# MAX3485_TXB0108PWR.net
KiCad netlist of a schematic drawn in Altium Designer
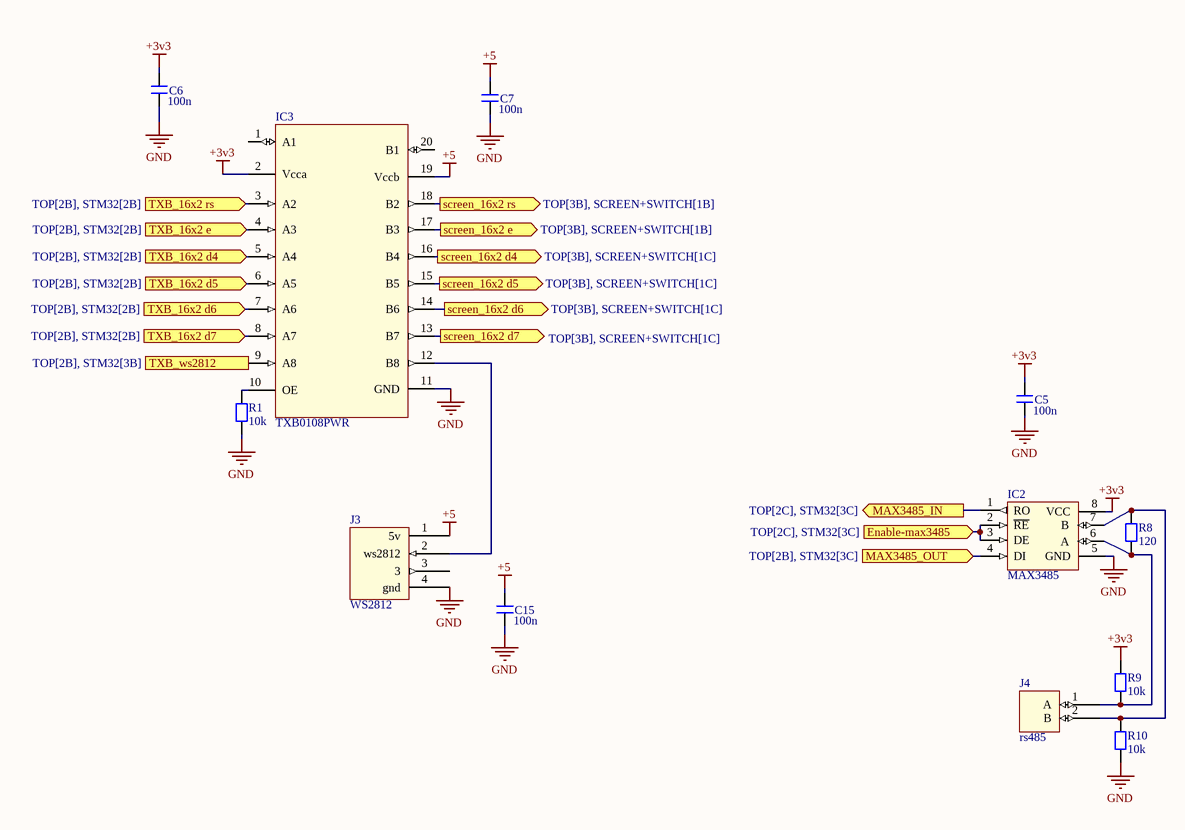
[diagram p0: MAX3485+TXB0108PWR.SchDoc]

(export (version "E")
  (design (tool "Eeschema 10.0.6"))
  (components
    (comp (ref "C5") (value "100n") (footprint "0805") (libsource (lib "capacitor") (part "capacitor")))
    (comp (ref "C6") (value "100n") (footprint "0805") (libsource (lib "capacitor") (part "capacitor")))
    (comp (ref "C7") (value "100n") (footprint "0805") (libsource (lib "capacitor") (part "capacitor")))
    (comp (ref "C15") (value "100n") (footprint "0805") (libsource (lib "capacitor") (part "capacitor")))
    (comp (ref "IC2") (value "MAX3485") (footprint "MAX3485") (libsource (lib "MAX3485") (part "MAX3485")))
    (comp (ref "IC3")
      (value "TXB0108PWR")
      (footprint "TXB0108PWR")
      (libsource (lib "TXB0108PWR") (part "TXB0108PWR"))
    )
    (comp (ref "J3") (value "WS2812") (footprint "4pinpwd") (libsource (lib "WS2812") (part "WS2812")))
    (comp (ref "J4") (value "rs485") (footprint "2pin") (libsource (lib "rs485") (part "rs485")))
    (comp (ref "R1") (value "10k") (footprint "0805") (libsource (lib "resistor") (part "resistor")))
    (comp (ref "R8") (value "120") (footprint "0805") (libsource (lib "resistor") (part "resistor")))
    (comp (ref "R9") (value "10k") (footprint "0805") (libsource (lib "resistor") (part "resistor")))
    (comp (ref "R10") (value "10k") (footprint "0805") (libsource (lib "resistor") (part "resistor")))
  )
  (nets
    (net (code "1") (name "+3v3") (class "Default")
      (node (ref "C5") (pin "1") (pinfunction "1_1") (pintype "passive"))
      (node (ref "C6") (pin "1") (pinfunction "1_1") (pintype "passive"))
      (node (ref "IC2") (pin "8") (pinfunction "VCC_8") (pintype "power_in"))
      (node (ref "IC3") (pin "2") (pinfunction "Vcca_2") (pintype "power_in"))
      (node (ref "R9") (pin "1") (pinfunction "1_1") (pintype "passive"))
    )
    (net (code "2") (name "+5") (class "Default")
      (node (ref "C15") (pin "1") (pinfunction "1_1") (pintype "passive"))
      (node (ref "C7") (pin "1") (pinfunction "1_1") (pintype "passive"))
      (node (ref "IC3") (pin "19") (pinfunction "Vccb_19") (pintype "power_in"))
      (node (ref "J3") (pin "1") (pinfunction "5v_1") (pintype "power_in"))
    )
    (net (code "3") (name "/Enable-max3485") (class "Default")
      (node (ref "IC2") (pin "2") (pinfunction "~{RE}_2") (pintype "input"))
      (node (ref "IC2") (pin "3") (pinfunction "DE_3") (pintype "input"))
    )
    (net (code "4") (name "/MAX3485_IN") (class "Default")
      (node (ref "IC2") (pin "1") (pinfunction "RO_1") (pintype "output"))
    )
    (net (code "5") (name "/MAX3485_OUT") (class "Default")
      (node (ref "IC2") (pin "4") (pinfunction "DI_4") (pintype "input"))
    )
    (net (code "6") (name "/TXB_16x2 d4") (class "Default")
      (node (ref "IC3") (pin "5") (pinfunction "A4_5") (pintype "input"))
    )
    (net (code "7") (name "/TXB_16x2 d5") (class "Default")
      (node (ref "IC3") (pin "6") (pinfunction "A5_6") (pintype "input"))
    )
    (net (code "8") (name "/TXB_16x2 d6") (class "Default")
      (node (ref "IC3") (pin "7") (pinfunction "A6_7") (pintype "input"))
    )
    (net (code "9") (name "/TXB_16x2 d7") (class "Default")
      (node (ref "IC3") (pin "8") (pinfunction "A7_8") (pintype "input"))
    )
    (net (code "10") (name "/TXB_16x2 e") (class "Default")
      (node (ref "IC3") (pin "4") (pinfunction "A3_4") (pintype "input"))
    )
    (net (code "11") (name "/TXB_16x2 rs") (class "Default")
      (node (ref "IC3") (pin "3") (pinfunction "A2_3") (pintype "input"))
    )
    (net (code "12") (name "/TXB_ws2812") (class "Default")
      (node (ref "IC3") (pin "9") (pinfunction "A8_9") (pintype "input"))
    )
    (net (code "13") (name "/screen_16x2 d4") (class "Default")
      (node (ref "IC3") (pin "16") (pinfunction "B4_16") (pintype "output"))
    )
    (net (code "14") (name "/screen_16x2 d5") (class "Default")
      (node (ref "IC3") (pin "15") (pinfunction "B5_15") (pintype "output"))
    )
    (net (code "15") (name "/screen_16x2 d6") (class "Default")
      (node (ref "IC3") (pin "14") (pinfunction "B6_14") (pintype "output"))
    )
    (net (code "16") (name "/screen_16x2 d7") (class "Default")
      (node (ref "IC3") (pin "13") (pinfunction "B7_13") (pintype "output"))
    )
    (net (code "17") (name "/screen_16x2 e") (class "Default")
      (node (ref "IC3") (pin "17") (pinfunction "B3_17") (pintype "output"))
    )
    (net (code "18") (name "/screen_16x2 rs") (class "Default")
      (node (ref "IC3") (pin "18") (pinfunction "B2_18") (pintype "output"))
    )
    (net (code "19") (name "GND") (class "Default")
      (node (ref "C15") (pin "2") (pintype "passive"))
      (node (ref "C5") (pin "2") (pintype "passive"))
      (node (ref "C6") (pin "2") (pintype "passive"))
      (node (ref "C7") (pin "2") (pintype "passive"))
      (node (ref "IC2") (pin "5") (pinfunction "GND_5") (pintype "power_in"))
      (node (ref "IC3") (pin "11") (pinfunction "GND_11") (pintype "power_in"))
      (node (ref "J3") (pin "4") (pinfunction "gnd_4") (pintype "power_in"))
      (node (ref "R1") (pin "2") (pinfunction "2_2") (pintype "passive"))
      (node (ref "R10") (pin "2") (pinfunction "2_2") (pintype "passive"))
    )
    (net (code "20") (name "Net-(IC2-A)") (class "Default")
      (node (ref "IC2") (pin "6") (pinfunction "A_6") (pintype "bidirectional"))
      (node (ref "J4") (pin "1") (pinfunction "A_1") (pintype "bidirectional"))
      (node (ref "R8") (pin "2") (pinfunction "2_2") (pintype "passive"))
      (node (ref "R9") (pin "2") (pinfunction "2_2") (pintype "passive"))
    )
    (net (code "21") (name "Net-(IC2-B)") (class "Default")
      (node (ref "IC2") (pin "7") (pinfunction "B_7") (pintype "bidirectional"))
      (node (ref "J4") (pin "2") (pinfunction "B_2") (pintype "bidirectional"))
      (node (ref "R10") (pin "1") (pinfunction "1_1") (pintype "passive"))
      (node (ref "R8") (pin "1") (pinfunction "1_1") (pintype "passive"))
    )
    (net (code "22") (name "Net-(IC3-B8)") (class "Default")
      (node (ref "IC3") (pin "12") (pinfunction "B8_12") (pintype "output"))
      (node (ref "J3") (pin "2") (pinfunction "ws2812_2") (pintype "input"))
    )
    (net (code "23") (name "Net-(IC3-OE)") (class "Default")
      (node (ref "IC3") (pin "10") (pinfunction "OE_10") (pintype "passive"))
      (node (ref "R1") (pin "1") (pinfunction "1_1") (pintype "passive"))
    )
    (net (code "24") (name "unconnected-(IC3-A1-Pad1)") (class "Default")
      (node (ref "IC3") (pin "1") (pinfunction "A1_1") (pintype "bidirectional"))
    )
    (net (code "25") (name "unconnected-(IC3-B1-Pad20)") (class "Default")
      (node (ref "IC3") (pin "20") (pinfunction "B1_20") (pintype "bidirectional"))
    )
    (net (code "26") (name "unconnected-(J3-Pad3)") (class "Default")
      (node (ref "J3") (pin "3") (pinfunction "3_3") (pintype "output"))
    )
  )
)
